# Master_Supply.net
KiCad netlist of a schematic drawn in Altium Designer
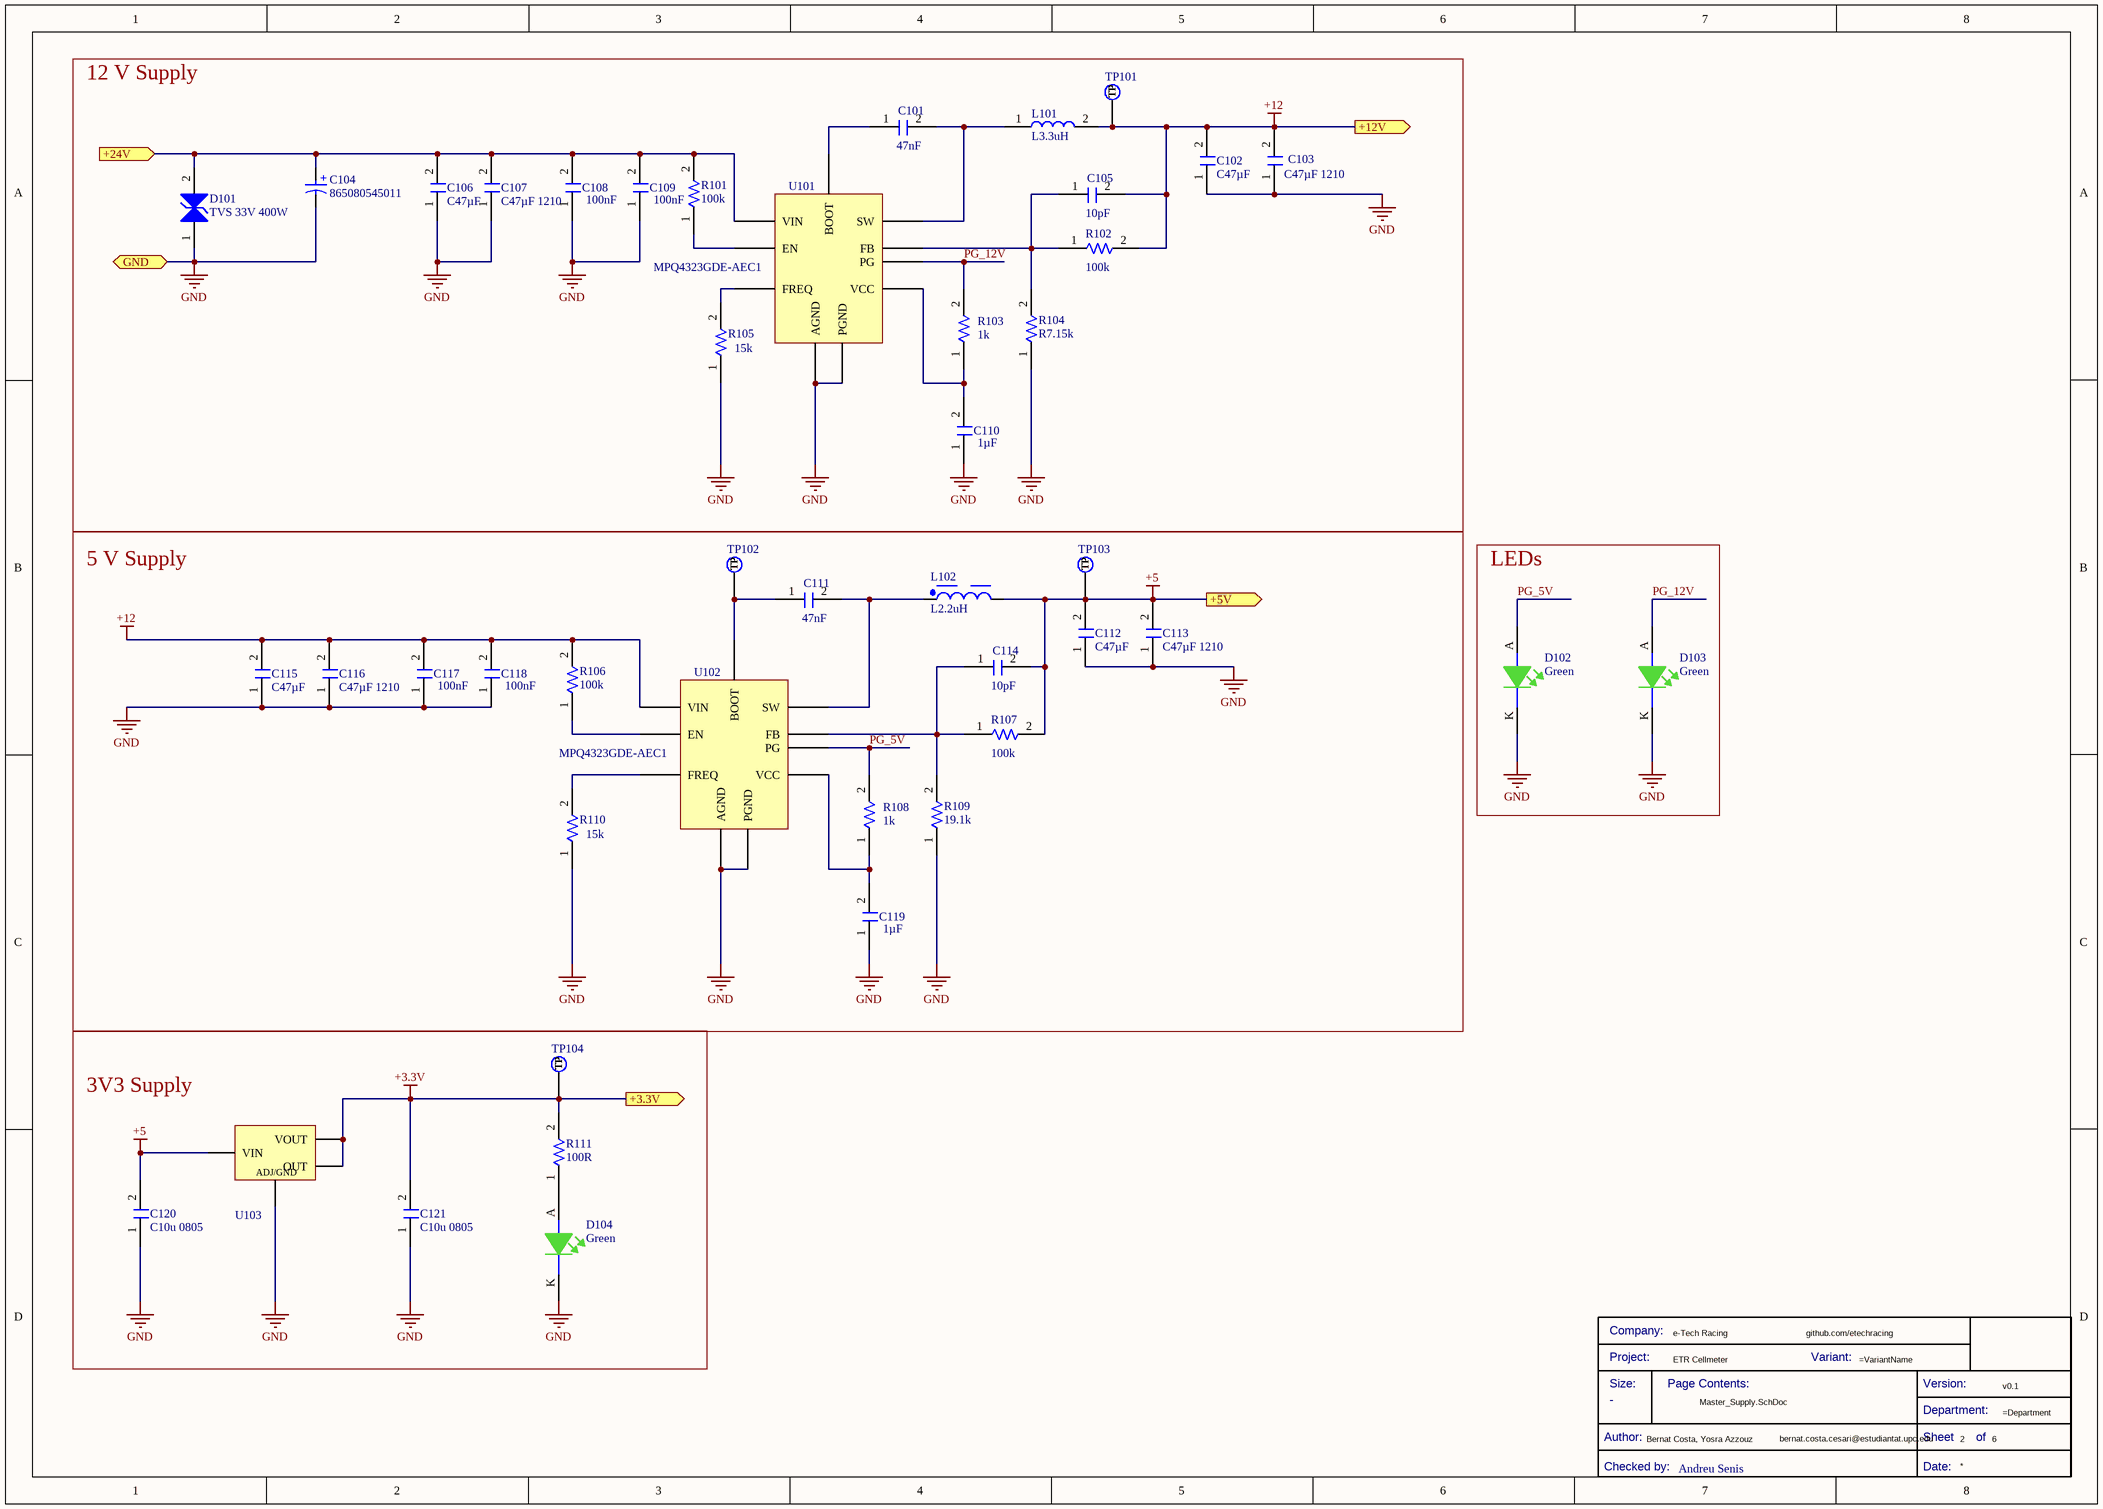
[diagram p0: Master_Supply.SchDoc]

(export (version "E")
  (design (tool "Eeschema 10.0.6"))
  (components
    (comp (ref "C101")
      (value "47nF")
      (footprint "WCAP-CSGP_0805_L2W1.25H0.8_Reflow")
      (description "Ceramic Capacitor, Ceramic. 885012207096")
      (fields (field (name "Comment") "C47nF_0805"))
      (libsource (lib "EMEA- E-Tech Racing- I'Escola d'Enginyeria de Barcelona Est") (part "C100p-50V-0805FNPC-C0G/NP0"))
    )
    (comp (ref "C102")
      (value "C47µF")
      (footprint "FP-GRM32E-0_3-0_2-IPC_C")
      (libsource (lib "EMEA- E-Tech Racing- I'Escola d'Enginyeria de Barcelona Est") (part "C100p-50V-0805FNPC-C0G/NP0"))
    )
    (comp (ref "C103")
      (value "C47µF 1210")
      (footprint "FP-GRM32E-0_3-0_2-IPC_C")
      (libsource (lib "EMEA- E-Tech Racing- I'Escola d'Enginyeria de Barcelona Est") (part "C100p-50V-0805FNPC-C0G/NP0"))
    )
    (comp (ref "C104")
      (value "865080545011")
      (footprint "WCAP-ASLI_D6.3H7.7")
      (description "WCAP-ASLI Aluminum Electrolytic Capacitor, V-Chip, D6.3 x H7.7mm, 68uF, 35V")
      (fields (field (name "MANUFACTURER") "Wurth Elektronik"))
      (libsource (lib "EMEA- E-Tech Racing- I'Escola d'Enginyeria de Barcelona Est") (part "865080545011"))
    )
    (comp (ref "C105")
      (value "10pF")
      (footprint "WCAP-CSGP_0805_L2W1.25H0.6_Reflow")
      (fields (field (name "Comment") "885012007051"))
      (libsource (lib "EMEA- E-Tech Racing- I'Escola d'Enginyeria de Barcelona Est") (part "C100p-50V-0805FNPC-C0G/NP0"))
    )
    (comp (ref "C106")
      (value "C47µF")
      (footprint "FP-GRM32E-0_3-0_2-IPC_C")
      (libsource (lib "EMEA- E-Tech Racing- I'Escola d'Enginyeria de Barcelona Est") (part "C100p-50V-0805FNPC-C0G/NP0"))
    )
    (comp (ref "C107")
      (value "C47µF 1210")
      (footprint "FP-GRM32E-0_3-0_2-IPC_C")
      (libsource (lib "EMEA- E-Tech Racing- I'Escola d'Enginyeria de Barcelona Est") (part "C100p-50V-0805FNPC-C0G/NP0"))
    )
    (comp (ref "C108")
      (value "100nF")
      (footprint "C0805FNPC-R")
      (description "Cap, 0.1ΜF, 50V, 10%, X7R, 0805")
      (fields
        (field (name "TOLERANCE") "10%")
        (field (name "Comment") "C100n-50V-0805FNPC-X7R")
        (field (name ".CREATOR") "DR")
      )
      (libsource (lib "EMEA- E-Tech Racing- I'Escola d'Enginyeria de Barcelona Est") (part "C100p-50V-0805FNPC-C0G/NP0"))
    )
    (comp (ref "C109")
      (value "100nF")
      (footprint "C0805FNPC-R")
      (description "Cap, 0.1ΜF, 50V, 10%, X7R, 0805")
      (fields
        (field (name "TOLERANCE") "10%")
        (field (name "Comment") "C100n-50V-0805FNPC-X7R")
        (field (name ".CREATOR") "DR")
      )
      (libsource (lib "EMEA- E-Tech Racing- I'Escola d'Enginyeria de Barcelona Est") (part "C100p-50V-0805FNPC-C0G/NP0"))
    )
    (comp (ref "C110")
      (value "1µF")
      (footprint "C0805FNPC-R")
      (fields
        (field (name "TOLERANCE") "10%")
        (field (name "Comment") "C1u-50V-0805FNPC-X7R")
        (field (name ".CREATOR") "GP")
      )
      (libsource (lib "EMEA- E-Tech Racing- I'Escola d'Enginyeria de Barcelona Est") (part "C100p-50V-0805FNPC-C0G/NP0"))
    )
    (comp (ref "C111")
      (value "47nF")
      (footprint "WCAP-CSGP_0805_L2W1.25H0.8_Reflow")
      (description "Ceramic Capacitor, Ceramic")
      (fields (field (name "Comment") "885012207096"))
      (libsource (lib "EMEA- E-Tech Racing- I'Escola d'Enginyeria de Barcelona Est") (part "C100p-50V-0805FNPC-C0G/NP0"))
    )
    (comp (ref "C112")
      (value "C47µF")
      (footprint "FP-GRM32E-0_3-0_2-IPC_C")
      (libsource (lib "EMEA- E-Tech Racing- I'Escola d'Enginyeria de Barcelona Est") (part "C100p-50V-0805FNPC-C0G/NP0"))
    )
    (comp (ref "C113")
      (value "C47µF 1210")
      (footprint "FP-GRM32E-0_3-0_2-IPC_C")
      (libsource (lib "EMEA- E-Tech Racing- I'Escola d'Enginyeria de Barcelona Est") (part "C100p-50V-0805FNPC-C0G/NP0"))
    )
    (comp (ref "C114")
      (value "10pF")
      (footprint "WCAP-CSGP_0805_L2W1.25H0.6_Reflow")
      (fields (field (name "Comment") "C10pF_0805_50V"))
      (libsource (lib "EMEA- E-Tech Racing- I'Escola d'Enginyeria de Barcelona Est") (part "C100p-50V-0805FNPC-C0G/NP0"))
    )
    (comp (ref "C115")
      (value "C47µF")
      (footprint "FP-GRM32E-0_3-0_2-IPC_C")
      (libsource (lib "EMEA- E-Tech Racing- I'Escola d'Enginyeria de Barcelona Est") (part "C100p-50V-0805FNPC-C0G/NP0"))
    )
    (comp (ref "C116")
      (value "C47µF 1210")
      (footprint "FP-GRM32E-0_3-0_2-IPC_C")
      (libsource (lib "EMEA- E-Tech Racing- I'Escola d'Enginyeria de Barcelona Est") (part "C100p-50V-0805FNPC-C0G/NP0"))
    )
    (comp (ref "C117")
      (value "100nF")
      (footprint "C0805FNPC-R")
      (description "Cap, 0.1ΜF, 50V, 10%, X7R, 0805")
      (fields
        (field (name "TOLERANCE") "10%")
        (field (name "Comment") "C100n-50V-0805FNPC-X7R")
        (field (name ".CREATOR") "DR")
      )
      (libsource (lib "EMEA- E-Tech Racing- I'Escola d'Enginyeria de Barcelona Est") (part "C100p-50V-0805FNPC-C0G/NP0"))
    )
    (comp (ref "C118")
      (value "100nF")
      (footprint "C0805FNPC-R")
      (description "Cap, 0.1ΜF, 50V, 10%, X7R, 0805")
      (fields
        (field (name "TOLERANCE") "10%")
        (field (name "Comment") "C100n-50V-0805FNPC-X7R")
        (field (name ".CREATOR") "DR")
      )
      (libsource (lib "EMEA- E-Tech Racing- I'Escola d'Enginyeria de Barcelona Est") (part "C100p-50V-0805FNPC-C0G/NP0"))
    )
    (comp (ref "C119")
      (value "1µF")
      (footprint "C0805FNPC-R")
      (fields
        (field (name "TOLERANCE") "10%")
        (field (name "Comment") "C1u-50V-0805FNPC-X7R")
        (field (name ".CREATOR") "GP")
      )
      (libsource (lib "EMEA- E-Tech Racing- I'Escola d'Enginyeria de Barcelona Est") (part "C100p-50V-0805FNPC-C0G/NP0"))
    )
    (comp (ref "C120")
      (value "C10u 0805")
      (footprint "C0805FNPC-R")
      (fields (field (name "TOLERANCE") "20%") (field (name ".CREATOR") "DR"))
      (libsource (lib "EMEA- E-Tech Racing- I'Escola d'Enginyeria de Barcelona Est") (part "C100p-50V-0805FNPC-C0G/NP0"))
    )
    (comp (ref "C121")
      (value "C10u 0805")
      (footprint "C0805FNPC-R")
      (fields (field (name "TOLERANCE") "20%") (field (name ".CREATOR") "DR"))
      (libsource (lib "EMEA- E-Tech Racing- I'Escola d'Enginyeria de Barcelona Est") (part "C100p-50V-0805FNPC-C0G/NP0"))
    )
    (comp (ref "D101")
      (value "TVS 33V 400W")
      (footprint "WE-TVSP_DO-214AC_Bidirectional")
      (description "Trans Voltage Suppressor Diode, 400W, Bidirectional, 1 Element, Silicon, DO-214AC")
      (libsource (lib "EMEA- E-Tech Racing- I'Escola d'Enginyeria de Barcelona Est") (part "WE-TVSP_Bidirectional"))
    )
    (comp (ref "D102")
      (value "150080VS75000")
      (footprint "LED_0805_WE")
      (description "Led, Green, 570 Nm, 2 V, 30 Ma, 40 Mcd Rohs Compliant: Yes")
      (fields (field (name "COLOR") "Green") (field (name ".CREATOR") "DR"))
      (libsource (lib "Semiconductor") (part "LEDVS-0805-40"))
    )
    (comp (ref "D103")
      (value "150080VS75000")
      (footprint "LED_0805_WE")
      (description "Led, Green, 570 Nm, 2 V, 30 Ma, 40 Mcd Rohs Compliant: Yes")
      (fields (field (name "COLOR") "Green") (field (name ".CREATOR") "DR"))
      (libsource (lib "Semiconductor") (part "LEDVS-0805-40"))
    )
    (comp (ref "D104")
      (value "150080VS75000")
      (footprint "LED_0805_WE")
      (description "Led, Green, 570 Nm, 2 V, 30 Ma, 40 Mcd Rohs Compliant: Yes")
      (fields (field (name "COLOR") "Green") (field (name ".CREATOR") "DR"))
      (libsource (lib "Semiconductor") (part "LEDVS-0805-40"))
    )
    (comp (ref "L101")
      (value "L3.3uH")
      (footprint "WE-PD_7345")
      (description "General Purpose Inductor, 3.3uH, 20%, 1 Element, Ferrite-Core, SMD. 744777003")
      (fields (field (name "TOLERANCE") "20%"))
      (libsource (lib "EMEA- E-Tech Racing- I'Escola d'Enginyeria de Barcelona Est") (part "L47u-60mA_CF"))
    )
    (comp (ref "L102")
      (value "L2.2uH")
      (footprint "WE-PD_7345")
      (description "General Purpose Inductor, 2.2uH, 20%, 1 Element, Ferrite-Core, SMD. 744777002")
      (fields (field (name "TOLERANCE") "20%"))
      (libsource (lib "EMEA- E-Tech Racing- I'Escola d'Enginyeria de Barcelona Est") (part "Inductor - 2"))
    )
    (comp (ref "R101")
      (value "100k")
      (footprint "RESC2013X70X40NL20T20")
      (fields
        (field (name "POWER") "125mW")
        (field (name "TOLERANCE") "5%")
        (field (name "Comment") "R100k-0805")
      )
      (libsource (lib "EMEA- E-Tech Racing- I'Escola d'Enginyeria de Barcelona Est") (part "R9.09K-1206FTK"))
    )
    (comp (ref "R102")
      (value "100k")
      (footprint "RESC2013X70X40NL20T20")
      (fields
        (field (name "POWER") "125mW")
        (field (name "TOLERANCE") "5%")
        (field (name "Comment") "R100k-0805")
      )
      (libsource (lib "EMEA- E-Tech Racing- I'Escola d'Enginyeria de Barcelona Est") (part "R9.09K-1206FTK"))
    )
    (comp (ref "R103")
      (value "1k")
      (footprint "R0805FTK")
      (description "Res Thick Film 0805 1K Ohm 5% 1/8W ±200ppm/°C Molded SMD SMD Paper Tape on Plastic Reel")
      (fields
        (field (name "TOLERANCE") "5%")
        (field (name "Comment") "R1k-0805FTK")
        (field (name ".CREATOR") "GP")
      )
      (libsource (lib "EMEA- E-Tech Racing- I'Escola d'Enginyeria de Barcelona Est") (part "R9.09K-1206FTK"))
    )
    (comp (ref "R104")
      (value "R7.15k")
      (footprint "FP-RN732A-IPC_B")
      (description "Fixed Resistor, Thin Film, 0.1W, 7150ohm, 100V, 0.1% +/-Tol, 10ppm/Cel, Surface Mount, 0805")
      (fields (field (name "TOLERANCE") "0.1%") (field (name "POWER") "100mW"))
      (libsource (lib "EMEA- E-Tech Racing- I'Escola d'Enginyeria de Barcelona Est") (part "R9.09K-1206FTK"))
    )
    (comp (ref "R105")
      (value "15k")
      (footprint "RESC2013X50X30ML20T20")
      (fields
        (field (name "POWER") "125mW")
        (field (name "TOLERANCE") "1%")
        (field (name "Comment") "R15K-0805")
      )
      (libsource (lib "EMEA- E-Tech Racing- I'Escola d'Enginyeria de Barcelona Est") (part "R9.09K-1206FTK"))
    )
    (comp (ref "R106")
      (value "100k")
      (footprint "RESC2013X70X40NL20T20")
      (fields
        (field (name "POWER") "125mW")
        (field (name "TOLERANCE") "5%")
        (field (name "Comment") "R100k-0805")
      )
      (libsource (lib "EMEA- E-Tech Racing- I'Escola d'Enginyeria de Barcelona Est") (part "R9.09K-1206FTK"))
    )
    (comp (ref "R107")
      (value "100k")
      (footprint "RESC2013X70X40NL20T20")
      (fields
        (field (name "POWER") "125mW")
        (field (name "TOLERANCE") "5%")
        (field (name "Comment") "R100k-0805")
      )
      (libsource (lib "EMEA- E-Tech Racing- I'Escola d'Enginyeria de Barcelona Est") (part "R9.09K-1206FTK"))
    )
    (comp (ref "R108")
      (value "1k")
      (footprint "R0805FTK")
      (description "Res Thick Film 0805 1K Ohm 5% 1/8W ±200ppm/°C Molded SMD SMD Paper Tape on Plastic Reel")
      (fields
        (field (name "TOLERANCE") "5%")
        (field (name "Comment") "R1k-0805FTK")
        (field (name ".CREATOR") "GP")
      )
      (libsource (lib "EMEA- E-Tech Racing- I'Escola d'Enginyeria de Barcelona Est") (part "R9.09K-1206FTK"))
    )
    (comp (ref "R109")
      (value "19.1k")
      (footprint "0805")
      (fields
        (field (name "TOLERANCE") "0.1%")
        (field (name "POWER") "125mW")
        (field (name "Comment") "R19.1k_0805")
      )
      (libsource (lib "EMEA- E-Tech Racing- I'Escola d'Enginyeria de Barcelona Est") (part "R9.09K-1206FTK"))
    )
    (comp (ref "R110")
      (value "15k")
      (footprint "RESC2013X50X30ML20T20")
      (fields
        (field (name "POWER") "125mW")
        (field (name "TOLERANCE") "1%")
        (field (name "Comment") "R15K-0805")
      )
      (libsource (lib "EMEA- E-Tech Racing- I'Escola d'Enginyeria de Barcelona Est") (part "R9.09K-1206FTK"))
    )
    (comp (ref "R111")
      (value "CR0805-FX-1000ELF")
      (footprint "R0805FTK")
      (description "Res Thick Film 0805 100 Ohm 1% 1/8W ±100ppm/°C Molded SMD SMD Paper Tape on Plastic Reel")
      (fields
        (field (name "TOLERANCE") "1%")
        (field (name "RESISTANCE") "100R")
        (field (name ".CREATOR") "DR")
      )
      (libsource (lib "Passives") (part "R100-0805FTK"))
    )
    (comp (ref "TP101")
      (value "TestPoint")
      (footprint "TestPoint")
      (description "Test Point 1x1 mm")
      (fields (field (name ".SCHCHECK") "GP") (field (name ".CREATOR") "GP") (field (name ".PCBCHECK") "GP"))
      (libsource (lib "EMEA- E-Tech Racing- I'Escola d'Enginyeria de Barcelona Est") (part "TestPoint"))
    )
    (comp (ref "TP102")
      (value "TestPoint")
      (footprint "TestPoint")
      (description "Test Point 1x1 mm")
      (fields (field (name ".SCHCHECK") "GP") (field (name ".CREATOR") "GP") (field (name ".PCBCHECK") "GP"))
      (libsource (lib "EMEA- E-Tech Racing- I'Escola d'Enginyeria de Barcelona Est") (part "TestPoint"))
    )
    (comp (ref "TP103")
      (value "TestPoint")
      (footprint "TestPoint")
      (description "Test Point 1x1 mm")
      (fields (field (name ".SCHCHECK") "GP") (field (name ".CREATOR") "GP") (field (name ".PCBCHECK") "GP"))
      (libsource (lib "EMEA- E-Tech Racing- I'Escola d'Enginyeria de Barcelona Est") (part "TestPoint"))
    )
    (comp (ref "TP104")
      (value "TestPoint")
      (footprint "TestPoint")
      (description "Test Point 1x1 mm")
      (fields (field (name ".SCHCHECK") "GP") (field (name ".CREATOR") "GP") (field (name ".PCBCHECK") "GP"))
      (libsource (lib "EMEA- E-Tech Racing- I'Escola d'Enginyeria de Barcelona Est") (part "TestPoint"))
    )
    (comp (ref "U101")
      (value "MPQ4323GDE-AEC1")
      (footprint "MPQ4323")
      (description "MPQ4323 – 42V LOAD DUMP, 3A, LOW IQ, SYNC STEP-DOWN CONVERTER, AEC-Q100")
      (libsource (lib "EMEA- E-Tech Racing- I'Escola d'Enginyeria de Barcelona Est") (part "MPQ4323"))
    )
    (comp (ref "U102")
      (value "MPQ4323GDE-AEC1")
      (footprint "MPQ4323")
      (description "MPQ4323 – 42V LOAD DUMP, 3A, LOW IQ, SYNC STEP-DOWN CONVERTER, AEC-Q100")
      (libsource (lib "EMEA- E-Tech Racing- I'Escola d'Enginyeria de Barcelona Est") (part "MPQ4323"))
    )
    (comp (ref "U103")
      (value "LM1117IMP-3.3/NOPB")
      (footprint "LDO_10V-0.8/3V3-SOT223")
      (description "LDO Regulator Pos 3.3V 0.8A 4-Pin(3+Tab) SOT-223 T/R / IC REG LDO 3.3V 0.8A SOT223")
      (fields (field (name "MANUFACTURER") "Texas Instruments") (field (name ".CREATOR") "GP"))
      (libsource (lib "Semiconductor") (part "LDO_10V-0.8/3V3-SOT223"))
    )
  )
  (nets
    (net (code "1") (name "+3.3V") (class "Default")
      (node (ref "C121") (pin "2") (pinfunction "2_2") (pintype "passive"))
      (node (ref "R111") (pin "2") (pinfunction "2_2") (pintype "passive"))
      (node (ref "TP104") (pin "1") (pinfunction "TP_1") (pintype "passive"))
      (node (ref "U103") (pin "2") (pinfunction "OUT_2") (pintype "passive"))
      (node (ref "U103") (pin "4") (pinfunction "VOUT_4") (pintype "passive"))
    )
    (net (code "2") (name "+5") (class "Default")
      (node (ref "C112") (pin "2") (pinfunction "2_2") (pintype "passive"))
      (node (ref "C113") (pin "2") (pinfunction "2_2") (pintype "passive"))
      (node (ref "C114") (pin "2") (pinfunction "2_2") (pintype "passive"))
      (node (ref "C120") (pin "2") (pinfunction "2_2") (pintype "passive"))
      (node (ref "L102") (pin "2") (pinfunction "2_2") (pintype "passive"))
      (node (ref "R107") (pin "2") (pinfunction "2_2") (pintype "passive"))
      (node (ref "TP103") (pin "1") (pinfunction "TP_1") (pintype "passive"))
      (node (ref "U103") (pin "3") (pinfunction "VIN_3") (pintype "passive"))
    )
    (net (code "3") (name "+12") (class "Default")
      (node (ref "C102") (pin "2") (pinfunction "2_2") (pintype "passive"))
      (node (ref "C103") (pin "2") (pinfunction "2_2") (pintype "passive"))
      (node (ref "C105") (pin "2") (pinfunction "2_2") (pintype "passive"))
      (node (ref "C115") (pin "2") (pinfunction "2_2") (pintype "passive"))
      (node (ref "C116") (pin "2") (pinfunction "2_2") (pintype "passive"))
      (node (ref "C117") (pin "2") (pinfunction "2_2") (pintype "passive"))
      (node (ref "C118") (pin "2") (pinfunction "2_2") (pintype "passive"))
      (node (ref "L101") (pin "2") (pinfunction "2_2") (pintype "passive"))
      (node (ref "R102") (pin "2") (pinfunction "2_2") (pintype "passive"))
      (node (ref "R106") (pin "2") (pinfunction "2_2") (pintype "passive"))
      (node (ref "TP101") (pin "1") (pinfunction "TP_1") (pintype "passive"))
      (node (ref "U102") (pin "1") (pinfunction "VIN_1") (pintype "passive"))
    )
    (net (code "4") (name "/+24V") (class "Default")
      (node (ref "C104") (pin "1") (pinfunction "P_1") (pintype "passive"))
      (node (ref "C106") (pin "2") (pinfunction "2_2") (pintype "passive"))
      (node (ref "C107") (pin "2") (pinfunction "2_2") (pintype "passive"))
      (node (ref "C108") (pin "2") (pinfunction "2_2") (pintype "passive"))
      (node (ref "C109") (pin "2") (pinfunction "2_2") (pintype "passive"))
      (node (ref "D101") (pin "2") (pinfunction "2_2") (pintype "passive"))
      (node (ref "R101") (pin "2") (pinfunction "2_2") (pintype "passive"))
      (node (ref "U101") (pin "1") (pinfunction "VIN_1") (pintype "passive"))
    )
    (net (code "5") (name "/PG_5V") (class "Default")
      (node (ref "D102") (pin "A") (pinfunction "A_A") (pintype "passive"))
      (node (ref "R108") (pin "2") (pinfunction "2_2") (pintype "passive"))
      (node (ref "U102") (pin "7") (pinfunction "PG_7") (pintype "passive"))
    )
    (net (code "6") (name "/PG_12V") (class "Default")
      (node (ref "D103") (pin "A") (pinfunction "A_A") (pintype "passive"))
      (node (ref "R103") (pin "2") (pinfunction "2_2") (pintype "passive"))
      (node (ref "U101") (pin "7") (pinfunction "PG_7") (pintype "passive"))
    )
    (net (code "7") (name "GND") (class "Default")
      (node (ref "C102") (pin "1") (pinfunction "1_1") (pintype "passive"))
      (node (ref "C103") (pin "1") (pinfunction "1_1") (pintype "passive"))
      (node (ref "C104") (pin "2") (pinfunction "N_2") (pintype "passive"))
      (node (ref "C106") (pin "1") (pinfunction "1_1") (pintype "passive"))
      (node (ref "C107") (pin "1") (pinfunction "1_1") (pintype "passive"))
      (node (ref "C108") (pin "1") (pinfunction "1_1") (pintype "passive"))
      (node (ref "C109") (pin "1") (pinfunction "1_1") (pintype "passive"))
      (node (ref "C110") (pin "1") (pinfunction "1_1") (pintype "passive"))
      (node (ref "C112") (pin "1") (pinfunction "1_1") (pintype "passive"))
      (node (ref "C113") (pin "1") (pinfunction "1_1") (pintype "passive"))
      (node (ref "C115") (pin "1") (pinfunction "1_1") (pintype "passive"))
      (node (ref "C116") (pin "1") (pinfunction "1_1") (pintype "passive"))
      (node (ref "C117") (pin "1") (pinfunction "1_1") (pintype "passive"))
      (node (ref "C118") (pin "1") (pinfunction "1_1") (pintype "passive"))
      (node (ref "C119") (pin "1") (pinfunction "1_1") (pintype "passive"))
      (node (ref "C120") (pin "1") (pinfunction "1_1") (pintype "passive"))
      (node (ref "C121") (pin "1") (pinfunction "1_1") (pintype "passive"))
      (node (ref "D101") (pin "1") (pinfunction "1_1") (pintype "passive"))
      (node (ref "D102") (pin "K") (pinfunction "K_K") (pintype "passive"))
      (node (ref "D103") (pin "K") (pinfunction "K_K") (pintype "passive"))
      (node (ref "D104") (pin "K") (pinfunction "K_K") (pintype "passive"))
      (node (ref "R104") (pin "1") (pinfunction "1_1") (pintype "passive"))
      (node (ref "R105") (pin "1") (pinfunction "1_1") (pintype "passive"))
      (node (ref "R109") (pin "1") (pinfunction "1_1") (pintype "passive"))
      (node (ref "R110") (pin "1") (pinfunction "1_1") (pintype "passive"))
      (node (ref "U101") (pin "4") (pinfunction "AGND_4") (pintype "passive"))
      (node (ref "U101") (pin "5") (pinfunction "PGND_5") (pintype "passive"))
      (node (ref "U102") (pin "4") (pinfunction "AGND_4") (pintype "passive"))
      (node (ref "U102") (pin "5") (pinfunction "PGND_5") (pintype "passive"))
      (node (ref "U103") (pin "1") (pinfunction "ADJ/GND_1") (pintype "passive"))
    )
    (net (code "8") (name "Net-(D104-PadA)") (class "Default")
      (node (ref "D104") (pin "A") (pinfunction "A_A") (pintype "passive"))
      (node (ref "R111") (pin "1") (pinfunction "1_1") (pintype "passive"))
    )
    (net (code "9") (name "Net-(TP102-TP)") (class "Default")
      (node (ref "C111") (pin "1") (pinfunction "1_1") (pintype "passive"))
      (node (ref "TP102") (pin "1") (pinfunction "TP_1") (pintype "passive"))
      (node (ref "U102") (pin "10") (pinfunction "BOOT_10") (pintype "passive"))
    )
    (net (code "10") (name "Net-(U101-BOOT)") (class "Default")
      (node (ref "C101") (pin "1") (pinfunction "1_1") (pintype "passive"))
      (node (ref "U101") (pin "10") (pinfunction "BOOT_10") (pintype "passive"))
    )
    (net (code "11") (name "Net-(U101-EN)") (class "Default")
      (node (ref "R101") (pin "1") (pinfunction "1_1") (pintype "passive"))
      (node (ref "U101") (pin "2") (pinfunction "EN_2") (pintype "passive"))
    )
    (net (code "12") (name "Net-(U101-FB)") (class "Default")
      (node (ref "C105") (pin "1") (pinfunction "1_1") (pintype "passive"))
      (node (ref "R102") (pin "1") (pinfunction "1_1") (pintype "passive"))
      (node (ref "R104") (pin "2") (pinfunction "2_2") (pintype "passive"))
      (node (ref "U101") (pin "8") (pinfunction "FB_8") (pintype "passive"))
    )
    (net (code "13") (name "Net-(U101-FREQ)") (class "Default")
      (node (ref "R105") (pin "2") (pinfunction "2_2") (pintype "passive"))
      (node (ref "U101") (pin "3") (pinfunction "FREQ_3") (pintype "passive"))
    )
    (net (code "14") (name "Net-(U101-SW)") (class "Default")
      (node (ref "C101") (pin "2") (pinfunction "2_2") (pintype "passive"))
      (node (ref "L101") (pin "1") (pinfunction "1_1") (pintype "passive"))
      (node (ref "U101") (pin "9") (pinfunction "SW_9") (pintype "passive"))
    )
    (net (code "15") (name "Net-(U101-VCC)") (class "Default")
      (node (ref "C110") (pin "2") (pinfunction "2_2") (pintype "passive"))
      (node (ref "R103") (pin "1") (pinfunction "1_1") (pintype "passive"))
      (node (ref "U101") (pin "6") (pinfunction "VCC_6") (pintype "passive"))
    )
    (net (code "16") (name "Net-(U102-EN)") (class "Default")
      (node (ref "R106") (pin "1") (pinfunction "1_1") (pintype "passive"))
      (node (ref "U102") (pin "2") (pinfunction "EN_2") (pintype "passive"))
    )
    (net (code "17") (name "Net-(U102-FB)") (class "Default")
      (node (ref "C114") (pin "1") (pinfunction "1_1") (pintype "passive"))
      (node (ref "R107") (pin "1") (pinfunction "1_1") (pintype "passive"))
      (node (ref "R109") (pin "2") (pinfunction "2_2") (pintype "passive"))
      (node (ref "U102") (pin "8") (pinfunction "FB_8") (pintype "passive"))
    )
    (net (code "18") (name "Net-(U102-FREQ)") (class "Default")
      (node (ref "R110") (pin "2") (pinfunction "2_2") (pintype "passive"))
      (node (ref "U102") (pin "3") (pinfunction "FREQ_3") (pintype "passive"))
    )
    (net (code "19") (name "Net-(U102-SW)") (class "Default")
      (node (ref "C111") (pin "2") (pinfunction "2_2") (pintype "passive"))
      (node (ref "L102") (pin "1") (pinfunction "1_1") (pintype "passive"))
      (node (ref "U102") (pin "9") (pinfunction "SW_9") (pintype "passive"))
    )
    (net (code "20") (name "Net-(U102-VCC)") (class "Default")
      (node (ref "C119") (pin "2") (pinfunction "2_2") (pintype "passive"))
      (node (ref "R108") (pin "1") (pinfunction "1_1") (pintype "passive"))
      (node (ref "U102") (pin "6") (pinfunction "VCC_6") (pintype "passive"))
    )
  )
)
